# Sheet_MCU.net
KiCad netlist of a schematic drawn in Altium Designer
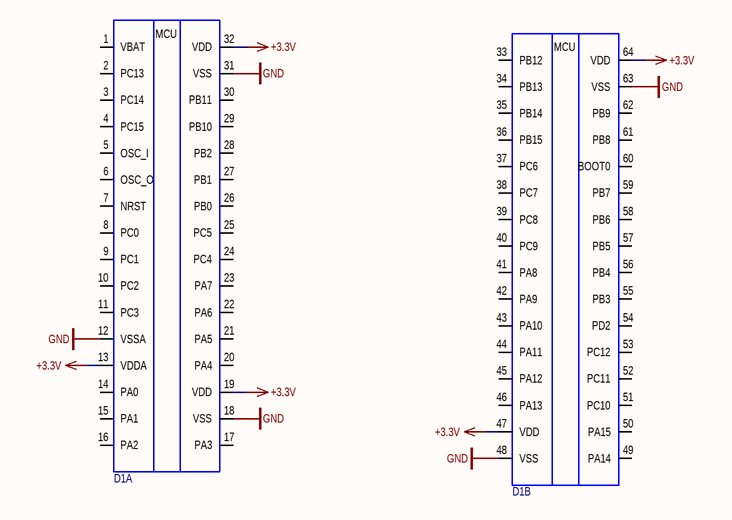
[diagram p0: Sheet_MCU.SchDoc]

(export (version "E")
  (design (tool "Eeschema 10.0.6"))
  (components
    (comp (ref "D1")
      (value "STM32f107RCT6")
      (footprint "LQFP-64")
      (libsource (lib "Integrated_Library_Smart_Switchboard") (part "STM32f107RCT6"))
    )
  )
  (nets
    (net (code "1") (name "+3.3V") (class "Default")
      (node (ref "D1") (pin "13") (pinfunction "VDDA_13") (pintype "passive"))
      (node (ref "D1") (pin "19") (pinfunction "VDD_19") (pintype "passive"))
      (node (ref "D1") (pin "32") (pinfunction "VDD_32") (pintype "passive"))
      (node (ref "D1") (pin "47") (pinfunction "VDD_47") (pintype "passive"))
      (node (ref "D1") (pin "64") (pinfunction "VDD_64") (pintype "passive"))
    )
    (net (code "2") (name "GND") (class "Default")
      (node (ref "D1") (pin "12") (pinfunction "VSSA_12") (pintype "passive"))
      (node (ref "D1") (pin "18") (pinfunction "VSS_18") (pintype "passive"))
      (node (ref "D1") (pin "31") (pinfunction "VSS_31") (pintype "passive"))
      (node (ref "D1") (pin "48") (pinfunction "VSS_48") (pintype "passive"))
      (node (ref "D1") (pin "63") (pinfunction "VSS_63") (pintype "passive"))
    )
    (net (code "3") (name "unconnected-(D1A-NRST-Pad7)") (class "Default")
      (node (ref "D1") (pin "7") (pinfunction "NRST_7") (pintype "passive"))
    )
    (net (code "4") (name "unconnected-(D1A-OSC_I-Pad5)") (class "Default")
      (node (ref "D1") (pin "5") (pinfunction "OSC_I_5") (pintype "passive"))
    )
    (net (code "5") (name "unconnected-(D1A-OSC_O-Pad6)") (class "Default")
      (node (ref "D1") (pin "6") (pinfunction "OSC_O_6") (pintype "passive"))
    )
    (net (code "6") (name "unconnected-(D1A-PA0-Pad14)") (class "Default")
      (node (ref "D1") (pin "14") (pinfunction "PA0_14") (pintype "passive"))
    )
    (net (code "7") (name "unconnected-(D1A-PA1-Pad15)") (class "Default")
      (node (ref "D1") (pin "15") (pinfunction "PA1_15") (pintype "passive"))
    )
    (net (code "8") (name "unconnected-(D1A-PA2-Pad16)") (class "Default")
      (node (ref "D1") (pin "16") (pinfunction "PA2_16") (pintype "passive"))
    )
    (net (code "9") (name "unconnected-(D1A-PA3-Pad17)") (class "Default")
      (node (ref "D1") (pin "17") (pinfunction "PA3_17") (pintype "passive"))
    )
    (net (code "10") (name "unconnected-(D1A-PA4-Pad20)") (class "Default")
      (node (ref "D1") (pin "20") (pinfunction "PA4_20") (pintype "passive"))
    )
    (net (code "11") (name "unconnected-(D1A-PA5-Pad21)") (class "Default")
      (node (ref "D1") (pin "21") (pinfunction "PA5_21") (pintype "passive"))
    )
    (net (code "12") (name "unconnected-(D1A-PA6-Pad22)") (class "Default")
      (node (ref "D1") (pin "22") (pinfunction "PA6_22") (pintype "passive"))
    )
    (net (code "13") (name "unconnected-(D1A-PA7-Pad23)") (class "Default")
      (node (ref "D1") (pin "23") (pinfunction "PA7_23") (pintype "passive"))
    )
    (net (code "14") (name "unconnected-(D1A-PB0-Pad26)") (class "Default")
      (node (ref "D1") (pin "26") (pinfunction "PB0_26") (pintype "passive"))
    )
    (net (code "15") (name "unconnected-(D1A-PB1-Pad27)") (class "Default")
      (node (ref "D1") (pin "27") (pinfunction "PB1_27") (pintype "passive"))
    )
    (net (code "16") (name "unconnected-(D1A-PB2-Pad28)") (class "Default")
      (node (ref "D1") (pin "28") (pinfunction "PB2_28") (pintype "passive"))
    )
    (net (code "17") (name "unconnected-(D1A-PB10-Pad29)") (class "Default")
      (node (ref "D1") (pin "29") (pinfunction "PB10_29") (pintype "passive"))
    )
    (net (code "18") (name "unconnected-(D1A-PB11-Pad30)") (class "Default")
      (node (ref "D1") (pin "30") (pinfunction "PB11_30") (pintype "passive"))
    )
    (net (code "19") (name "unconnected-(D1A-PC0-Pad8)") (class "Default")
      (node (ref "D1") (pin "8") (pinfunction "PC0_8") (pintype "passive"))
    )
    (net (code "20") (name "unconnected-(D1A-PC1-Pad9)") (class "Default")
      (node (ref "D1") (pin "9") (pinfunction "PC1_9") (pintype "passive"))
    )
    (net (code "21") (name "unconnected-(D1A-PC2-Pad10)") (class "Default")
      (node (ref "D1") (pin "10") (pinfunction "PC2_10") (pintype "passive"))
    )
    (net (code "22") (name "unconnected-(D1A-PC3-Pad11)") (class "Default")
      (node (ref "D1") (pin "11") (pinfunction "PC3_11") (pintype "passive"))
    )
    (net (code "23") (name "unconnected-(D1A-PC4-Pad24)") (class "Default")
      (node (ref "D1") (pin "24") (pinfunction "PC4_24") (pintype "passive"))
    )
    (net (code "24") (name "unconnected-(D1A-PC5-Pad25)") (class "Default")
      (node (ref "D1") (pin "25") (pinfunction "PC5_25") (pintype "passive"))
    )
    (net (code "25") (name "unconnected-(D1A-PC13-Pad2)") (class "Default")
      (node (ref "D1") (pin "2") (pinfunction "PC13_2") (pintype "passive"))
    )
    (net (code "26") (name "unconnected-(D1A-PC14-Pad3)") (class "Default")
      (node (ref "D1") (pin "3") (pinfunction "PC14_3") (pintype "passive"))
    )
    (net (code "27") (name "unconnected-(D1A-PC15-Pad4)") (class "Default")
      (node (ref "D1") (pin "4") (pinfunction "PC15_4") (pintype "passive"))
    )
    (net (code "28") (name "unconnected-(D1A-VBAT-Pad1)") (class "Default")
      (node (ref "D1") (pin "1") (pinfunction "VBAT_1") (pintype "passive"))
    )
    (net (code "29") (name "unconnected-(D1B-BOOT0-Pad60)") (class "Default")
      (node (ref "D1") (pin "60") (pinfunction "BOOT0_60") (pintype "passive"))
    )
    (net (code "30") (name "unconnected-(D1B-PA8-Pad41)") (class "Default")
      (node (ref "D1") (pin "41") (pinfunction "PA8_41") (pintype "passive"))
    )
    (net (code "31") (name "unconnected-(D1B-PA9-Pad42)") (class "Default")
      (node (ref "D1") (pin "42") (pinfunction "PA9_42") (pintype "passive"))
    )
    (net (code "32") (name "unconnected-(D1B-PA10-Pad43)") (class "Default")
      (node (ref "D1") (pin "43") (pinfunction "PA10_43") (pintype "passive"))
    )
    (net (code "33") (name "unconnected-(D1B-PA11-Pad44)") (class "Default")
      (node (ref "D1") (pin "44") (pinfunction "PA11_44") (pintype "passive"))
    )
    (net (code "34") (name "unconnected-(D1B-PA12-Pad45)") (class "Default")
      (node (ref "D1") (pin "45") (pinfunction "PA12_45") (pintype "passive"))
    )
    (net (code "35") (name "unconnected-(D1B-PA13-Pad46)") (class "Default")
      (node (ref "D1") (pin "46") (pinfunction "PA13_46") (pintype "passive"))
    )
    (net (code "36") (name "unconnected-(D1B-PA14-Pad49)") (class "Default")
      (node (ref "D1") (pin "49") (pinfunction "PA14_49") (pintype "passive"))
    )
    (net (code "37") (name "unconnected-(D1B-PA15-Pad50)") (class "Default")
      (node (ref "D1") (pin "50") (pinfunction "PA15_50") (pintype "passive"))
    )
    (net (code "38") (name "unconnected-(D1B-PB3-Pad55)") (class "Default")
      (node (ref "D1") (pin "55") (pinfunction "PB3_55") (pintype "passive"))
    )
    (net (code "39") (name "unconnected-(D1B-PB4-Pad56)") (class "Default")
      (node (ref "D1") (pin "56") (pinfunction "PB4_56") (pintype "passive"))
    )
    (net (code "40") (name "unconnected-(D1B-PB5-Pad57)") (class "Default")
      (node (ref "D1") (pin "57") (pinfunction "PB5_57") (pintype "passive"))
    )
    (net (code "41") (name "unconnected-(D1B-PB6-Pad58)") (class "Default")
      (node (ref "D1") (pin "58") (pinfunction "PB6_58") (pintype "passive"))
    )
    (net (code "42") (name "unconnected-(D1B-PB7-Pad59)") (class "Default")
      (node (ref "D1") (pin "59") (pinfunction "PB7_59") (pintype "passive"))
    )
    (net (code "43") (name "unconnected-(D1B-PB8-Pad61)") (class "Default")
      (node (ref "D1") (pin "61") (pinfunction "PB8_61") (pintype "passive"))
    )
    (net (code "44") (name "unconnected-(D1B-PB9-Pad62)") (class "Default")
      (node (ref "D1") (pin "62") (pinfunction "PB9_62") (pintype "passive"))
    )
    (net (code "45") (name "unconnected-(D1B-PB12-Pad33)") (class "Default")
      (node (ref "D1") (pin "33") (pinfunction "PB12_33") (pintype "passive"))
    )
    (net (code "46") (name "unconnected-(D1B-PB13-Pad34)") (class "Default")
      (node (ref "D1") (pin "34") (pinfunction "PB13_34") (pintype "passive"))
    )
    (net (code "47") (name "unconnected-(D1B-PB14-Pad35)") (class "Default")
      (node (ref "D1") (pin "35") (pinfunction "PB14_35") (pintype "passive"))
    )
    (net (code "48") (name "unconnected-(D1B-PB15-Pad36)") (class "Default")
      (node (ref "D1") (pin "36") (pinfunction "PB15_36") (pintype "passive"))
    )
    (net (code "49") (name "unconnected-(D1B-PC6-Pad37)") (class "Default")
      (node (ref "D1") (pin "37") (pinfunction "PC6_37") (pintype "passive"))
    )
    (net (code "50") (name "unconnected-(D1B-PC7-Pad38)") (class "Default")
      (node (ref "D1") (pin "38") (pinfunction "PC7_38") (pintype "passive"))
    )
    (net (code "51") (name "unconnected-(D1B-PC8-Pad39)") (class "Default")
      (node (ref "D1") (pin "39") (pinfunction "PC8_39") (pintype "passive"))
    )
    (net (code "52") (name "unconnected-(D1B-PC9-Pad40)") (class "Default")
      (node (ref "D1") (pin "40") (pinfunction "PC9_40") (pintype "passive"))
    )
    (net (code "53") (name "unconnected-(D1B-PC10-Pad51)") (class "Default")
      (node (ref "D1") (pin "51") (pinfunction "PC10_51") (pintype "passive"))
    )
    (net (code "54") (name "unconnected-(D1B-PC11-Pad52)") (class "Default")
      (node (ref "D1") (pin "52") (pinfunction "PC11_52") (pintype "passive"))
    )
    (net (code "55") (name "unconnected-(D1B-PC12-Pad53)") (class "Default")
      (node (ref "D1") (pin "53") (pinfunction "PC12_53") (pintype "passive"))
    )
    (net (code "56") (name "unconnected-(D1B-PD2-Pad54)") (class "Default")
      (node (ref "D1") (pin "54") (pinfunction "PD2_54") (pintype "passive"))
    )
  )
)
